# 1.net
KiCad netlist of a schematic drawn in Altium Designer
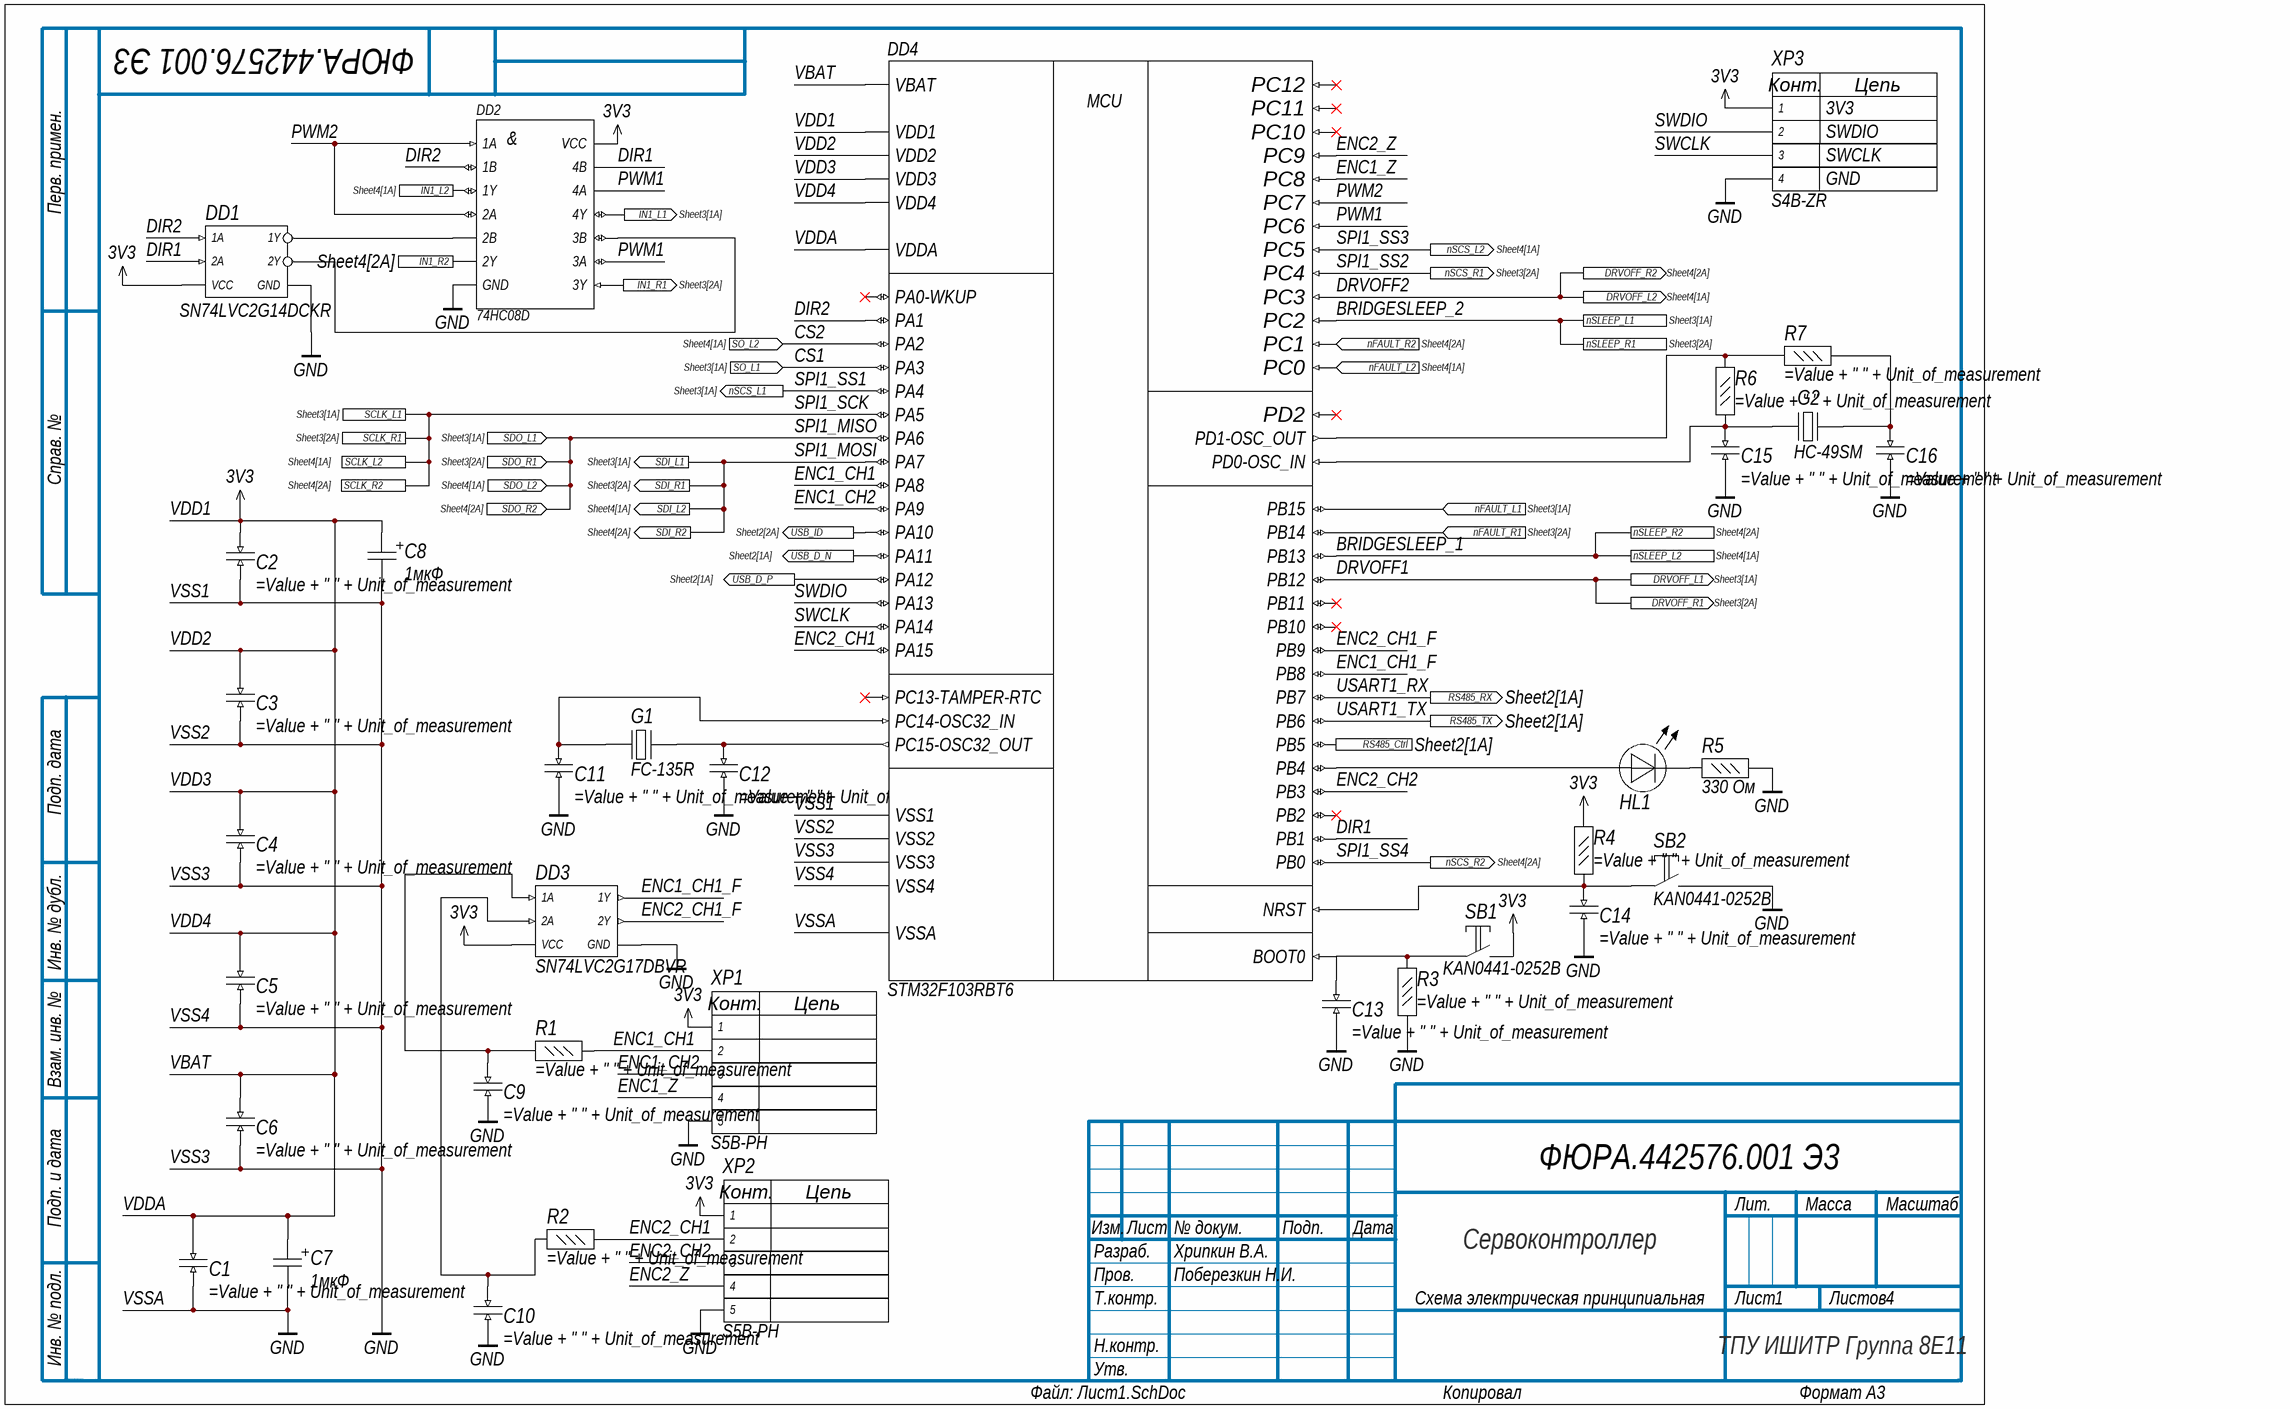
[diagram p0: Лист1.SchDoc]

(export (version "E")
  (design (tool "Eeschema 10.0.6"))
  (components
    (comp (ref "C1")
      (value "100нФ")
      (footprint "CAP_0603")
      (description "Конденсатор керамический, типоразмера 0603")
      (libsource (lib "PassiveComponents") (part "CAP_0603"))
    )
    (comp (ref "C2")
      (value "100нФ")
      (footprint "CAP_0603")
      (description "Конденсатор керамический, типоразмера 0603")
      (libsource (lib "PassiveComponents") (part "CAP_0603"))
    )
    (comp (ref "C3")
      (value "100нФ")
      (footprint "CAP_0603")
      (description "Конденсатор керамический, типоразмера 0603")
      (libsource (lib "PassiveComponents") (part "CAP_0603"))
    )
    (comp (ref "C4")
      (value "100нФ")
      (footprint "CAP_0603")
      (description "Конденсатор керамический, типоразмера 0603")
      (libsource (lib "PassiveComponents") (part "CAP_0603"))
    )
    (comp (ref "C5")
      (value "100нФ")
      (footprint "CAP_0603")
      (description "Конденсатор керамический, типоразмера 0603")
      (libsource (lib "PassiveComponents") (part "CAP_0603"))
    )
    (comp (ref "C6")
      (value "100нФ")
      (footprint "CAP_0603")
      (description "Конденсатор керамический, типоразмера 0603")
      (libsource (lib "PassiveComponents") (part "CAP_0603"))
    )
    (comp (ref "C7")
      (value "1мкФ")
      (footprint "TECAP_A")
      (description "Описание свойств компонента")
      (libsource (lib "PassiveComponents") (part "TECAP_A"))
    )
    (comp (ref "C8")
      (value "1мкФ")
      (footprint "TECAP_A")
      (description "Описание свойств компонента")
      (libsource (lib "PassiveComponents") (part "TECAP_A"))
    )
    (comp (ref "C9")
      (value "10пФ")
      (footprint "CAP_0603")
      (description "Конденсатор керамический, типоразмера 0603")
      (libsource (lib "PassiveComponents") (part "CAP_0603"))
    )
    (comp (ref "C10")
      (value "10пФ")
      (footprint "CAP_0603")
      (description "Конденсатор керамический, типоразмера 0603")
      (libsource (lib "PassiveComponents") (part "CAP_0603"))
    )
    (comp (ref "C11")
      (value "20пФ")
      (footprint "CAP_0603")
      (description "Конденсатор керамический, типоразмера 0603")
      (libsource (lib "PassiveComponents") (part "CAP_0603"))
    )
    (comp (ref "C12")
      (value "20пФ")
      (footprint "CAP_0603")
      (description "Конденсатор керамический, типоразмера 0603")
      (libsource (lib "PassiveComponents") (part "CAP_0603"))
    )
    (comp (ref "C13")
      (value "100нФ")
      (footprint "CAP_0603")
      (description "Конденсатор керамический, типоразмера 0603")
      (libsource (lib "PassiveComponents") (part "CAP_0603"))
    )
    (comp (ref "C14")
      (value "100нФ")
      (footprint "CAP_0603")
      (description "Конденсатор керамический, типоразмера 0603")
      (libsource (lib "PassiveComponents") (part "CAP_0603"))
    )
    (comp (ref "C15")
      (value "20пФ")
      (footprint "CAP_0603")
      (description "Конденсатор керамический, типоразмера 0603")
      (libsource (lib "PassiveComponents") (part "CAP_0603"))
    )
    (comp (ref "C16")
      (value "20пФ")
      (footprint "CAP_0603")
      (description "Конденсатор керамический, типоразмера 0603")
      (libsource (lib "PassiveComponents") (part "CAP_0603"))
    )
    (comp (ref "DD1")
      (value "SN74LVC2G14DCKR")
      (footprint "SOT363 (SC70-6)")
      (description "Сдвоенный инвертор с триггером Шмидта")
      (libsource (lib "ICs") (part "SN74LVC2G14DCKR"))
    )
    (comp (ref "DD2")
      (value "74HC08D")
      (footprint "SO14")
      (description "Логическая ИС, QUAD 2-INPUT AND GATE")
      (libsource (lib "ICs") (part "74HC08D"))
    )
    (comp (ref "DD3")
      (value "SN74LVC2G17DBVR")
      (footprint "SOT23-6")
      (description "Сдвоенный буфер с триггером Шмитта на входе")
      (libsource (lib "ICs") (part "SN74LVC2G17DBVR"))
    )
    (comp (ref "DD4")
      (value "STM32F103RBT6")
      (footprint "LQFP-64")
      (description "Микроконтроллер 32-Бит, Cortex-M3, 72МГц, 128КБ Flash, USB, CAN [LQFP-64]")
      (libsource (lib "ICs") (part "STM32F103RBT6"))
    )
    (comp (ref "G1")
      (value "FC-135R")
      (footprint "FC-135R")
      (description "Кварцевый резонатор 32,768 кГц; SMD")
      (libsource (lib "Complicated") (part "FC-135R"))
    )
    (comp (ref "G2")
      (value "HC-49SM")
      (footprint "HC-49SM")
      (description "Кварцевый резонатор 8 МГц; SMD")
      (libsource (lib "Complicated") (part "HC-49SM"))
    )
    (comp (ref "HL1") (value "3") (footprint "LED_0805") (libsource (lib "Complicated") (part "LED_0805_O")))
    (comp (ref "R1")
      (value "100кОм")
      (footprint "RES_0603")
      (description "Резистор, типоразмера 0603")
      (libsource (lib "") (part "RES_0603_1"))
    )
    (comp (ref "R2")
      (value "100кОм")
      (footprint "RES_0603")
      (description "Резистор, типоразмера 0603")
      (libsource (lib "") (part "RES_0603_1"))
    )
    (comp (ref "R3")
      (value "10кОм")
      (footprint "RES_0603")
      (description "Резистор, типоразмера 0603")
      (libsource (lib "") (part "RES_0603_2"))
    )
    (comp (ref "R4")
      (value "10кОм")
      (footprint "RES_0603")
      (description "Резистор, типоразмера 0603")
      (libsource (lib "SimpleComponents") (part "RES_0603"))
    )
    (comp (ref "R5")
      (value "330 Ом")
      (footprint "RES_0603")
      (description "Резистор, типоразмера 0603")
      (libsource (lib "") (part "RES_0603_1"))
    )
    (comp (ref "R6")
      (value "1МОм")
      (footprint "RES_0603")
      (description "Резистор, типоразмера 0603")
      (libsource (lib "SimpleComponents") (part "RES_0603"))
    )
    (comp (ref "R7")
      (value "100кОм")
      (footprint "RES_0603")
      (description "Резистор, типоразмера 0603")
      (libsource (lib "") (part "RES_0603_1"))
    )
    (comp (ref "SB1")
      (value "KAN0441-0252B")
      (footprint "SMD-BUTTON_6x3.5")
      (description "Описание свойств компонента")
      (libsource (lib "PassiveComponents") (part "SMD-Button_6x3.5"))
    )
    (comp (ref "SB2")
      (value "KAN0441-0252B")
      (footprint "SMD-BUTTON_6x3.5")
      (description "Описание свойств компонента")
      (libsource (lib "PassiveComponents") (part "SMD-Button_6x3.5"))
    )
    (comp (ref "XP1")
      (value "S5B-PH")
      (footprint "S5B-PH-K-S")
      (description "JST PH 5pin 2 mm pitch; horizontal; through hole OR full smd; S5B-PH-SM4-TB")
      (libsource (lib "SimpleComponents") (part "S5B-PH"))
    )
    (comp (ref "XP2")
      (value "S5B-PH")
      (footprint "S5B-PH-K-S")
      (description "JST PH 5pin 2 mm pitch; horizontal; through hole OR full smd; S5B-PH-SM4-TB")
      (libsource (lib "SimpleComponents") (part "S5B-PH"))
    )
    (comp (ref "XP3")
      (value "S4B-ZR")
      (footprint "S4B-ZR-SM4A-TF")
      (description "JST ZH 4pin 1.5 mm pitch; horizontal; through hole OR full smd; S4B-ZR")
      (libsource (lib "PassiveComponents") (part "S4B-ZR"))
    )
  )
  (nets
    (net (code "1") (name "/BRIDGESLEEP_1") (class "Default")
      (node (ref "DD4") (pin "34") (pinfunction "PB13_34") (pintype "bidirectional"))
    )
    (net (code "2") (name "/BRIDGESLEEP_2") (class "Default")
      (node (ref "DD4") (pin "10") (pinfunction "PC2_10") (pintype "input"))
    )
    (net (code "3") (name "/CS1") (class "Default")
      (node (ref "DD4") (pin "17") (pinfunction "PA3_17") (pintype "bidirectional"))
    )
    (net (code "4") (name "/CS2") (class "Default")
      (node (ref "DD4") (pin "16") (pinfunction "PA2_16") (pintype "bidirectional"))
    )
    (net (code "5") (name "/DIR1") (class "Default")
      (node (ref "DD1") (pin "3") (pinfunction "2A_3") (pintype "input"))
      (node (ref "DD2") (pin "13") (pinfunction "4B_13") (pintype "power_in"))
      (node (ref "DD4") (pin "27") (pinfunction "PB1_27") (pintype "bidirectional"))
    )
    (net (code "6") (name "/DIR2") (class "Default")
      (node (ref "DD1") (pin "1") (pinfunction "1A_1") (pintype "input"))
      (node (ref "DD2") (pin "2") (pinfunction "1B_2") (pintype "bidirectional"))
      (node (ref "DD4") (pin "15") (pinfunction "PA1_15") (pintype "bidirectional"))
    )
    (net (code "7") (name "/DRVOFF1") (class "Default")
      (node (ref "DD4") (pin "33") (pinfunction "PB12_33") (pintype "bidirectional"))
    )
    (net (code "8") (name "/DRVOFF2") (class "Default")
      (node (ref "DD4") (pin "11") (pinfunction "PC3_11") (pintype "input"))
    )
    (net (code "9") (name "/ENC1_CH1") (class "Default")
      (node (ref "DD4") (pin "41") (pinfunction "PA8_41") (pintype "bidirectional"))
      (node (ref "R1") (pin "2") (pinfunction "2_2") (pintype "passive"))
      (node (ref "XP1") (pin "2") (pinfunction "2_2") (pintype "passive"))
    )
    (net (code "10") (name "/ENC1_CH1_F") (class "Default")
      (node (ref "DD3") (pin "6") (pinfunction "1Y_6") (pintype "output"))
      (node (ref "DD4") (pin "61") (pinfunction "PB8_61") (pintype "bidirectional"))
    )
    (net (code "11") (name "/ENC1_CH2") (class "Default")
      (node (ref "DD4") (pin "42") (pinfunction "PA9_42") (pintype "bidirectional"))
      (node (ref "XP1") (pin "3") (pinfunction "3_3") (pintype "passive"))
    )
    (net (code "12") (name "/ENC1_Z") (class "Default")
      (node (ref "DD4") (pin "39") (pinfunction "PC8_39") (pintype "input"))
      (node (ref "XP1") (pin "4") (pinfunction "4_4") (pintype "passive"))
    )
    (net (code "13") (name "/ENC2_CH1") (class "Default")
      (node (ref "DD4") (pin "50") (pinfunction "PA15_50") (pintype "bidirectional"))
      (node (ref "R2") (pin "2") (pinfunction "2_2") (pintype "passive"))
      (node (ref "XP2") (pin "2") (pinfunction "2_2") (pintype "passive"))
    )
    (net (code "14") (name "/ENC2_CH1_F") (class "Default")
      (node (ref "DD3") (pin "4") (pinfunction "2Y_4") (pintype "output"))
      (node (ref "DD4") (pin "62") (pinfunction "PB9_62") (pintype "bidirectional"))
    )
    (net (code "15") (name "/ENC2_CH2") (class "Default")
      (node (ref "DD4") (pin "55") (pinfunction "PB3_55") (pintype "bidirectional"))
      (node (ref "XP2") (pin "3") (pinfunction "3_3") (pintype "passive"))
    )
    (net (code "16") (name "/ENC2_Z") (class "Default")
      (node (ref "DD4") (pin "40") (pinfunction "PC9_40") (pintype "input"))
      (node (ref "XP2") (pin "4") (pinfunction "4_4") (pintype "passive"))
    )
    (net (code "17") (name "/IN1_L1") (class "Default")
      (node (ref "DD2") (pin "11") (pinfunction "4Y_11") (pintype "bidirectional"))
    )
    (net (code "18") (name "/IN1_L2") (class "Default")
      (node (ref "DD2") (pin "3") (pinfunction "1Y_3") (pintype "bidirectional"))
    )
    (net (code "19") (name "/IN1_R1") (class "Default")
      (node (ref "DD2") (pin "8") (pinfunction "3Y_8") (pintype "input"))
    )
    (net (code "20") (name "/IN1_R2") (class "Default")
      (node (ref "DD2") (pin "6") (pinfunction "2Y_6") (pintype "power_in"))
    )
    (net (code "21") (name "/PWM1") (class "Default")
      (node (ref "DD2") (pin "12") (pinfunction "4A_12") (pintype "power_in"))
      (node (ref "DD2") (pin "9") (pinfunction "3A_9") (pintype "bidirectional"))
      (node (ref "DD4") (pin "37") (pinfunction "PC6_37") (pintype "input"))
    )
    (net (code "22") (name "/PWM2") (class "Default")
      (node (ref "DD2") (pin "1") (pinfunction "1A_1") (pintype "input"))
      (node (ref "DD2") (pin "4") (pinfunction "2A_4") (pintype "bidirectional"))
      (node (ref "DD4") (pin "38") (pinfunction "PC7_38") (pintype "input"))
    )
    (net (code "23") (name "/RS485_Ctrl") (class "Default")
      (node (ref "DD4") (pin "57") (pinfunction "PB5_57") (pintype "bidirectional"))
    )
    (net (code "24") (name "/SPI1_MISO") (class "Default")
      (node (ref "DD4") (pin "22") (pinfunction "PA6_22") (pintype "bidirectional"))
    )
    (net (code "25") (name "/SPI1_MOSI") (class "Default")
      (node (ref "DD4") (pin "23") (pinfunction "PA7_23") (pintype "bidirectional"))
    )
    (net (code "26") (name "/SPI1_SCK") (class "Default")
      (node (ref "DD4") (pin "21") (pinfunction "PA5_21") (pintype "bidirectional"))
    )
    (net (code "27") (name "/SPI1_SS1") (class "Default")
      (node (ref "DD4") (pin "20") (pinfunction "PA4_20") (pintype "bidirectional"))
    )
    (net (code "28") (name "/SPI1_SS2") (class "Default")
      (node (ref "DD4") (pin "24") (pinfunction "PC4_24") (pintype "input"))
    )
    (net (code "29") (name "/SPI1_SS3") (class "Default")
      (node (ref "DD4") (pin "25") (pinfunction "PC5_25") (pintype "input"))
    )
    (net (code "30") (name "/SPI1_SS4") (class "Default")
      (node (ref "DD4") (pin "26") (pinfunction "PB0_26") (pintype "bidirectional"))
    )
    (net (code "31") (name "/SWCLK") (class "Default")
      (node (ref "DD4") (pin "49") (pinfunction "PA14_49") (pintype "bidirectional"))
      (node (ref "XP3") (pin "3") (pinfunction "3_3") (pintype "passive"))
    )
    (net (code "32") (name "/SWDIO") (class "Default")
      (node (ref "DD4") (pin "46") (pinfunction "PA13_46") (pintype "bidirectional"))
      (node (ref "XP3") (pin "2") (pinfunction "2_2") (pintype "passive"))
    )
    (net (code "33") (name "/USART1_RX") (class "Default")
      (node (ref "DD4") (pin "59") (pinfunction "PB7_59") (pintype "bidirectional"))
    )
    (net (code "34") (name "/USART1_TX") (class "Default")
      (node (ref "DD4") (pin "58") (pinfunction "PB6_58") (pintype "bidirectional"))
    )
    (net (code "35") (name "/USB_D_N") (class "Default")
      (node (ref "DD4") (pin "44") (pinfunction "PA11_44") (pintype "bidirectional"))
    )
    (net (code "36") (name "/USB_D_P") (class "Default")
      (node (ref "DD4") (pin "45") (pinfunction "PA12_45") (pintype "bidirectional"))
    )
    (net (code "37") (name "/USB_ID") (class "Default")
      (node (ref "DD4") (pin "43") (pinfunction "PA10_43") (pintype "bidirectional"))
    )
    (net (code "38") (name "/nFAULT_L1") (class "Default")
      (node (ref "DD4") (pin "36") (pinfunction "PB15_36") (pintype "bidirectional"))
    )
    (net (code "39") (name "/nFAULT_L2") (class "Default")
      (node (ref "DD4") (pin "8") (pinfunction "PC0_8") (pintype "input"))
    )
    (net (code "40") (name "/nFAULT_R1") (class "Default")
      (node (ref "DD4") (pin "35") (pinfunction "PB14_35") (pintype "bidirectional"))
    )
    (net (code "41") (name "/nFAULT_R2") (class "Default")
      (node (ref "DD4") (pin "9") (pinfunction "PC1_9") (pintype "input"))
    )
    (net (code "42") (name "3V3") (class "Default")
      (node (ref "C1") (pin "2") (pintype "input"))
      (node (ref "C2") (pin "2") (pintype "input"))
      (node (ref "C3") (pin "2") (pintype "input"))
      (node (ref "C4") (pin "2") (pintype "input"))
      (node (ref "C5") (pin "2") (pintype "input"))
      (node (ref "C6") (pin "2") (pintype "input"))
      (node (ref "C7") (pin "1") (pintype "passive"))
      (node (ref "C8") (pin "1") (pintype "passive"))
      (node (ref "DD1") (pin "5") (pinfunction "VCC_5") (pintype "power_in"))
      (node (ref "DD2") (pin "14") (pinfunction "VCC_14") (pintype "power_in"))
      (node (ref "DD3") (pin "5") (pinfunction "VCC_5") (pintype "power_in"))
      (node (ref "DD4") (pin "1") (pinfunction "VBAT_1") (pintype "power_in"))
      (node (ref "DD4") (pin "13") (pinfunction "VDDA_13") (pintype "power_in"))
      (node (ref "DD4") (pin "19") (pinfunction "VDD1_19") (pintype "power_in"))
      (node (ref "DD4") (pin "32") (pinfunction "VDD2_32") (pintype "power_in"))
      (node (ref "DD4") (pin "48") (pinfunction "VDD3_48") (pintype "power_in"))
      (node (ref "DD4") (pin "64") (pinfunction "VDD4_64") (pintype "power_in"))
      (node (ref "R4") (pin "2") (pinfunction "2_2") (pintype "passive"))
      (node (ref "SB1") (pin "2") (pinfunction "S2_2") (pintype "passive"))
      (node (ref "XP1") (pin "1") (pinfunction "1_1") (pintype "passive"))
      (node (ref "XP2") (pin "1") (pinfunction "1_1") (pintype "passive"))
      (node (ref "XP3") (pin "1") (pinfunction "1_1") (pintype "passive"))
    )
    (net (code "43") (name "GND") (class "Default")
      (node (ref "C1") (pin "1") (pintype "input"))
      (node (ref "C10") (pin "1") (pintype "input"))
      (node (ref "C11") (pin "1") (pintype "input"))
      (node (ref "C12") (pin "1") (pintype "input"))
      (node (ref "C13") (pin "1") (pintype "input"))
      (node (ref "C14") (pin "1") (pintype "input"))
      (node (ref "C15") (pin "1") (pintype "input"))
      (node (ref "C16") (pin "1") (pintype "input"))
      (node (ref "C2") (pin "1") (pintype "input"))
      (node (ref "C3") (pin "1") (pintype "input"))
      (node (ref "C4") (pin "1") (pintype "input"))
      (node (ref "C5") (pin "1") (pintype "input"))
      (node (ref "C6") (pin "1") (pintype "input"))
      (node (ref "C7") (pin "2") (pintype "passive"))
      (node (ref "C8") (pin "2") (pintype "passive"))
      (node (ref "C9") (pin "1") (pintype "input"))
      (node (ref "DD1") (pin "2") (pinfunction "GND_2") (pintype "power_in"))
      (node (ref "DD2") (pin "7") (pinfunction "GND_7") (pintype "power_in"))
      (node (ref "DD3") (pin "2") (pinfunction "GND_2") (pintype "power_in"))
      (node (ref "DD4") (pin "12") (pinfunction "VSSA_12") (pintype "power_in"))
      (node (ref "DD4") (pin "18") (pinfunction "VSS1_18") (pintype "power_in"))
      (node (ref "DD4") (pin "31") (pinfunction "VSS2_31") (pintype "power_in"))
      (node (ref "DD4") (pin "47") (pinfunction "VSS3_47") (pintype "power_in"))
      (node (ref "DD4") (pin "63") (pinfunction "VSS4_63") (pintype "power_in"))
      (node (ref "R3") (pin "2") (pinfunction "2_2") (pintype "passive"))
      (node (ref "R5") (pin "2") (pinfunction "2_2") (pintype "passive"))
      (node (ref "SB2") (pin "2") (pinfunction "S2_2") (pintype "passive"))
      (node (ref "XP1") (pin "5") (pinfunction "5_5") (pintype "passive"))
      (node (ref "XP2") (pin "5") (pinfunction "5_5") (pintype "passive"))
      (node (ref "XP3") (pin "4") (pinfunction "4_4") (pintype "passive"))
    )
    (net (code "44") (name "Net-(C16-Pad2)") (class "Default")
      (node (ref "C16") (pin "2") (pintype "input"))
      (node (ref "G2") (pin "2") (pintype "passive"))
      (node (ref "R7") (pin "2") (pinfunction "2_2") (pintype "passive"))
    )
    (net (code "45") (name "Net-(DD1-1Y)") (class "Default")
      (node (ref "DD1") (pin "6") (pinfunction "1Y_6") (pintype "output"))
      (node (ref "DD2") (pin "5") (pinfunction "2B_5") (pintype "power_in"))
    )
    (net (code "46") (name "Net-(DD1-2Y)") (class "Default")
      (node (ref "DD1") (pin "4") (pinfunction "2Y_4") (pintype "output"))
      (node (ref "DD2") (pin "10") (pinfunction "3B_10") (pintype "bidirectional"))
    )
    (net (code "47") (name "Net-(DD3-1A)") (class "Default")
      (node (ref "C9") (pin "2") (pintype "input"))
      (node (ref "DD3") (pin "1") (pinfunction "1A_1") (pintype "input"))
      (node (ref "R1") (pin "1") (pinfunction "1_1") (pintype "passive"))
    )
    (net (code "48") (name "Net-(DD3-2A)") (class "Default")
      (node (ref "C10") (pin "2") (pintype "input"))
      (node (ref "DD3") (pin "3") (pinfunction "2A_3") (pintype "input"))
      (node (ref "R2") (pin "1") (pinfunction "1_1") (pintype "passive"))
    )
    (net (code "49") (name "Net-(DD4-BOOT0)") (class "Default")
      (node (ref "C13") (pin "2") (pintype "input"))
      (node (ref "DD4") (pin "60") (pinfunction "BOOT0_60") (pintype "input"))
      (node (ref "R3") (pin "1") (pinfunction "1_1") (pintype "passive"))
      (node (ref "SB1") (pin "1") (pinfunction "S1_1") (pintype "passive"))
    )
    (net (code "50") (name "Net-(DD4-NRST)") (class "Default")
      (node (ref "C14") (pin "2") (pintype "input"))
      (node (ref "DD4") (pin "7") (pinfunction "NRST_7") (pintype "input"))
      (node (ref "R4") (pin "1") (pinfunction "1_1") (pintype "passive"))
      (node (ref "SB2") (pin "1") (pinfunction "S1_1") (pintype "passive"))
    )
    (net (code "51") (name "Net-(DD4-PB4)") (class "Default")
      (node (ref "DD4") (pin "56") (pinfunction "PB4_56") (pintype "bidirectional"))
      (node (ref "HL1") (pin "A") (pinfunction "2_A") (pintype "passive"))
    )
    (net (code "52") (name "Net-(DD4-PC14-OSC32_IN)") (class "Default")
      (node (ref "C11") (pin "2") (pintype "input"))
      (node (ref "DD4") (pin "3") (pinfunction "PC14-OSC32_IN_3") (pintype "input"))
      (node (ref "G1") (pin "1") (pintype "passive"))
    )
    (net (code "53") (name "Net-(DD4-PC15-OSC32_OUT)") (class "Default")
      (node (ref "C12") (pin "2") (pintype "input"))
      (node (ref "DD4") (pin "4") (pinfunction "PC15-OSC32_OUT_4") (pintype "output"))
      (node (ref "G1") (pin "2") (pintype "passive"))
    )
    (net (code "54") (name "Net-(DD4-PD0-OSC_IN)") (class "Default")
      (node (ref "C15") (pin "2") (pintype "input"))
      (node (ref "DD4") (pin "5") (pinfunction "PD0-OSC_IN_5") (pintype "input"))
      (node (ref "G2") (pin "1") (pintype "passive"))
      (node (ref "R6") (pin "1") (pinfunction "1_1") (pintype "passive"))
    )
    (net (code "55") (name "Net-(DD4-PD1-OSC_OUT)") (class "Default")
      (node (ref "DD4") (pin "6") (pinfunction "PD1-OSC_OUT_6") (pintype "output"))
      (node (ref "R6") (pin "2") (pinfunction "2_2") (pintype "passive"))
      (node (ref "R7") (pin "1") (pinfunction "1_1") (pintype "passive"))
    )
    (net (code "56") (name "Net-(HL1-1)") (class "Default")
      (node (ref "HL1") (pin "C") (pinfunction "1_C") (pintype "passive"))
      (node (ref "R5") (pin "1") (pinfunction "1_1") (pintype "passive"))
    )
    (net (code "57") (name "unconnected-(DD4-PA0-WKUP-Pad14)") (class "Default")
      (node (ref "DD4") (pin "14") (pinfunction "PA0-WKUP_14") (pintype "bidirectional+no_connect"))
    )
    (net (code "58") (name "unconnected-(DD4-PB2-Pad28)") (class "Default")
      (node (ref "DD4") (pin "28") (pinfunction "PB2_28") (pintype "bidirectional+no_connect"))
    )
    (net (code "59") (name "unconnected-(DD4-PB10-Pad29)") (class "Default")
      (node (ref "DD4") (pin "29") (pinfunction "PB10_29") (pintype "bidirectional+no_connect"))
    )
    (net (code "60") (name "unconnected-(DD4-PB11-Pad30)") (class "Default")
      (node (ref "DD4") (pin "30") (pinfunction "PB11_30") (pintype "bidirectional+no_connect"))
    )
    (net (code "61") (name "unconnected-(DD4-PC10-Pad51)") (class "Default")
      (node (ref "DD4") (pin "51") (pinfunction "PC10_51") (pintype "input+no_connect"))
    )
    (net (code "62") (name "unconnected-(DD4-PC11-Pad52)") (class "Default")
      (node (ref "DD4") (pin "52") (pinfunction "PC11_52") (pintype "input+no_connect"))
    )
    (net (code "63") (name "unconnected-(DD4-PC12-Pad53)") (class "Default")
      (node (ref "DD4") (pin "53") (pinfunction "PC12_53") (pintype "input+no_connect"))
    )
    (net (code "64") (name "unconnected-(DD4-PC13-TAMPER-RTC-Pad2)") (class "Default")
      (node (ref "DD4") (pin "2") (pinfunction "PC13-TAMPER-RTC_2") (pintype "input+no_connect"))
    )
    (net (code "65") (name "unconnected-(DD4-PD2-Pad54)") (class "Default")
      (node (ref "DD4") (pin "54") (pinfunction "PD2_54") (pintype "input+no_connect"))
    )
  )
)
